# DotCrypt.net
KiCad netlist of a schematic drawn in EAGLE
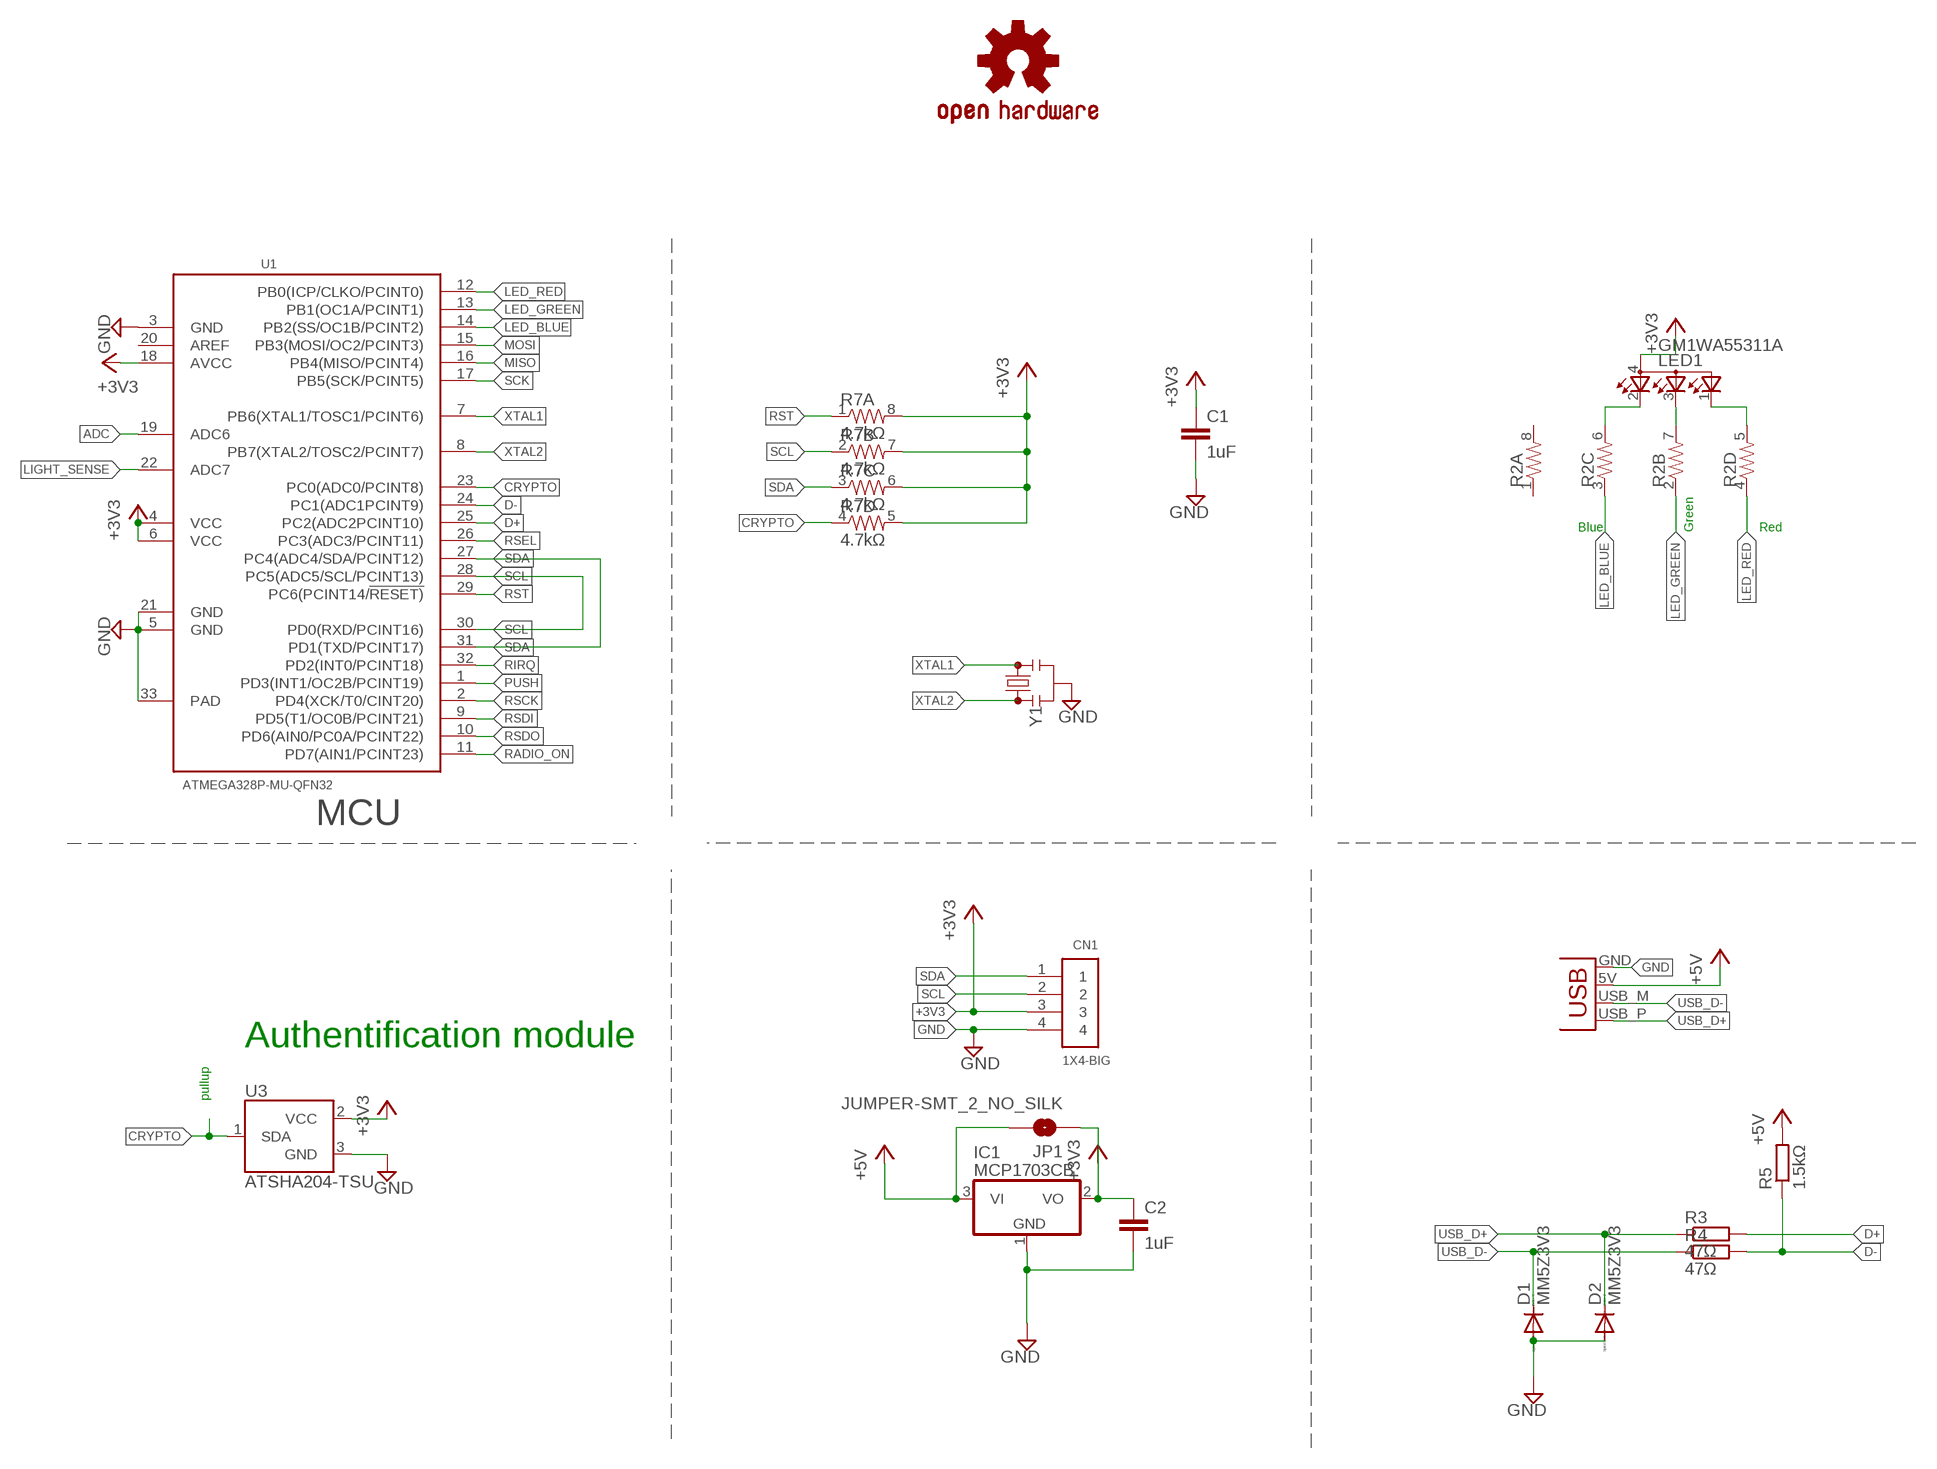
[diagram p0: schematic, sheet 1]

(export (version "E")
  (design (tool "Eeschema 10.0.6"))
  (components
    (comp (ref "C1")
      (value "1uF")
      (footprint "eagle-import:C0603")
      (libsource (lib "eagle-import") (part "C-EUC0603"))
    )
    (comp (ref "C2")
      (value "1uF")
      (footprint "eagle-import:C0603")
      (libsource (lib "eagle-import") (part "C-EUC0603"))
    )
    (comp (ref "CN1")
      (value "1X4-BIG")
      (footprint "eagle-import:1X04-BIG")
      (libsource (lib "eagle-import") (part "1X4-BIG"))
    )
    (comp (ref "D1")
      (value "MM5Z3V3")
      (footprint "eagle-import:SOD523")
      (libsource (lib "eagle-import") (part "DIODE-SOD523"))
    )
    (comp (ref "D2")
      (value "MM5Z3V3")
      (footprint "eagle-import:SOD523")
      (libsource (lib "eagle-import") (part "DIODE-SOD523"))
    )
    (comp (ref "IC1")
      (value "MCP1703CB")
      (footprint "eagle-import:SOT23")
      (libsource (lib "eagle-import") (part "MCP1703CB"))
    )
    (comp (ref "JP1")
      (value "JUMPER-SMT_2_NO_SILK")
      (footprint "eagle-import:SMT-JUMPER_2_NO_SILK")
      (libsource (lib "eagle-import") (part "JUMPER-SMT_2_NO_SILK"))
    )
    (comp (ref "JP3")
      (value "USBPCB")
      (footprint "eagle-import:USB-A-PCB")
      (libsource (lib "eagle-import") (part "USBPCB"))
    )
    (comp (ref "LED1")
      (value "GM1WA55311A")
      (footprint "eagle-import:GM1WA55311A")
      (libsource (lib "eagle-import") (part "GM1WA55311A"))
    )
    (comp (ref "LOGO1")
      (value "OSHW-LOGOS")
      (footprint "eagle-import:OSHW-LOGO-S")
      (libsource (lib "eagle-import") (part "OSHW-LOGOS"))
    )
    (comp (ref "R2")
      (value "RESISTOR-ARRAY0603-ARV")
      (footprint "eagle-import:0603-ARV")
      (libsource (lib "eagle-import") (part "RESISTOR-ARRAY0603-ARV"))
    )
    (comp (ref "R3")
      (value "47Ω")
      (footprint "eagle-import:R0603")
      (libsource (lib "eagle-import") (part "R-EU_R0603"))
    )
    (comp (ref "R4")
      (value "47Ω")
      (footprint "eagle-import:R0603")
      (libsource (lib "eagle-import") (part "R-EU_R0603"))
    )
    (comp (ref "R5")
      (value "1.5kΩ")
      (footprint "eagle-import:R0603")
      (libsource (lib "eagle-import") (part "R-EU_R0603"))
    )
    (comp (ref "R7")
      (value "4.7kΩ")
      (footprint "eagle-import:0603-ARV")
      (libsource (lib "eagle-import") (part "RESISTOR-ARRAY0603-ARV"))
    )
    (comp (ref "U1")
      (value "ATMEGA328P-MU-QFN32")
      (footprint "eagle-import:QFN32G-0.5-5X5MM")
      (fields (field (name "MPN") "ATMEGA328P-MU"))
      (libsource (lib "eagle-import") (part "MCU-ATMEGA328P-MU(QFN32)"))
    )
    (comp (ref "U3")
      (value "ATSHA204-TSU")
      (footprint "eagle-import:SOT23-3")
      (libsource (lib "eagle-import") (part "ATSHA204-TSU"))
    )
    (comp (ref "Y1")
      (value "RESONATORSMD-3.2X1.3")
      (footprint "eagle-import:RESONATOR-SMD-3.2X1.3")
      (libsource (lib "eagle-import") (part "RESONATORSMD-3.2X1.3"))
    )
  )
  (nets
    (net (code "1") (name "+3V3") (class "Default")
      (node (ref "C1") (pin "1") (pinfunction "1_1") (pintype "passive"))
      (node (ref "C2") (pin "1") (pinfunction "1_1") (pintype "passive"))
      (node (ref "CN1") (pin "3") (pinfunction "3_3") (pintype "bidirectional"))
      (node (ref "IC1") (pin "2") (pinfunction "VO_2") (pintype "passive"))
      (node (ref "JP1") (pin "1") (pinfunction "1_1") (pintype "passive"))
      (node (ref "LED1") (pin "4") (pinfunction "A_4") (pintype "passive"))
      (node (ref "R7") (pin "5") (pinfunction "2_5") (pintype "passive"))
      (node (ref "R7") (pin "6") (pinfunction "2_6") (pintype "passive"))
      (node (ref "R7") (pin "7") (pinfunction "2_7") (pintype "passive"))
      (node (ref "R7") (pin "8") (pinfunction "2_8") (pintype "passive"))
      (node (ref "U1") (pin "18") (pinfunction "AVCC_18") (pintype "bidirectional"))
      (node (ref "U1") (pin "4") (pinfunction "VCC_4") (pintype "bidirectional"))
      (node (ref "U1") (pin "6") (pinfunction "VCC_6") (pintype "bidirectional"))
      (node (ref "U3") (pin "2") (pinfunction "VCC_2") (pintype "bidirectional"))
    )
    (net (code "2") (name "+5V") (class "Default")
      (node (ref "IC1") (pin "3") (pinfunction "VI_3") (pintype "input"))
      (node (ref "JP1") (pin "2") (pinfunction "2_2") (pintype "passive"))
      (node (ref "JP3") (pin "5V") (pinfunction "VBUS_5V") (pintype "bidirectional"))
      (node (ref "R5") (pin "2") (pinfunction "2_2") (pintype "passive"))
    )
    (net (code "3") (name "ADC") (class "Default")
      (node (ref "U1") (pin "19") (pinfunction "ADC6_19") (pintype "bidirectional"))
    )
    (net (code "4") (name "CRYPTO") (class "Default")
      (node (ref "R7") (pin "4") (pinfunction "1_4") (pintype "passive"))
      (node (ref "U1") (pin "23") (pinfunction "PC0(ADC0/PCINT8)_23") (pintype "bidirectional"))
      (node (ref "U3") (pin "1") (pinfunction "SDA_1") (pintype "bidirectional"))
    )
    (net (code "5") (name "D+") (class "Default")
      (node (ref "R3") (pin "2") (pinfunction "2_2") (pintype "passive"))
      (node (ref "U1") (pin "25") (pinfunction "PC2(ADC2PCINT10)_25") (pintype "bidirectional"))
    )
    (net (code "6") (name "D-") (class "Default")
      (node (ref "R4") (pin "2") (pinfunction "2_2") (pintype "passive"))
      (node (ref "R5") (pin "1") (pinfunction "1_1") (pintype "passive"))
      (node (ref "U1") (pin "24") (pinfunction "PC1(ADC1PCINT9)_24") (pintype "bidirectional"))
    )
    (net (code "7") (name "GND") (class "Default")
      (node (ref "C1") (pin "2") (pinfunction "2_2") (pintype "passive"))
      (node (ref "C2") (pin "2") (pinfunction "2_2") (pintype "passive"))
      (node (ref "CN1") (pin "4") (pinfunction "4_4") (pintype "bidirectional"))
      (node (ref "D1") (pin "A") (pinfunction "A_A") (pintype "passive"))
      (node (ref "D2") (pin "A") (pinfunction "A_A") (pintype "passive"))
      (node (ref "IC1") (pin "1") (pinfunction "GND_1") (pintype "passive"))
      (node (ref "JP3") (pin "GND") (pinfunction "GND_GND") (pintype "bidirectional"))
      (node (ref "U1") (pin "21") (pinfunction "GND_21") (pintype "bidirectional"))
      (node (ref "U1") (pin "3") (pinfunction "GND_3") (pintype "bidirectional"))
      (node (ref "U1") (pin "33") (pinfunction "PAD_33") (pintype "bidirectional"))
      (node (ref "U1") (pin "5") (pinfunction "GND_5") (pintype "bidirectional"))
      (node (ref "U3") (pin "3") (pinfunction "GND_3") (pintype "bidirectional"))
      (node (ref "Y1") (pin "2") (pinfunction "2_2") (pintype "passive"))
    )
    (net (code "8") (name "LED_BLUE") (class "Default")
      (node (ref "R2") (pin "3") (pinfunction "1_3") (pintype "passive"))
      (node (ref "U1") (pin "14") (pinfunction "PB2(SS/OC1B/PCINT2)_14") (pintype "bidirectional"))
    )
    (net (code "9") (name "LED_GREEN") (class "Default")
      (node (ref "R2") (pin "2") (pinfunction "1_2") (pintype "passive"))
      (node (ref "U1") (pin "13") (pinfunction "PB1(OC1A/PCINT1)_13") (pintype "bidirectional"))
    )
    (net (code "10") (name "LED_RED") (class "Default")
      (node (ref "R2") (pin "4") (pinfunction "1_4") (pintype "passive"))
      (node (ref "U1") (pin "12") (pinfunction "PB0(ICP/CLKO/PCINT0)_12") (pintype "bidirectional"))
    )
    (net (code "11") (name "LIGHT_SENSE") (class "Default")
      (node (ref "U1") (pin "22") (pinfunction "ADC7_22") (pintype "bidirectional"))
    )
    (net (code "12") (name "MISO") (class "Default")
      (node (ref "U1") (pin "16") (pinfunction "PB4(MISO/PCINT4)_16") (pintype "bidirectional"))
    )
    (net (code "13") (name "MOSI") (class "Default")
      (node (ref "U1") (pin "15") (pinfunction "PB3(MOSI/OC2/PCINT3)_15") (pintype "bidirectional"))
    )
    (net (code "14") (name "Net-(LED1-CBLUE)") (class "Default")
      (node (ref "LED1") (pin "3") (pinfunction "CBLUE_3") (pintype "passive"))
      (node (ref "R2") (pin "7") (pinfunction "2_7") (pintype "passive"))
    )
    (net (code "15") (name "Net-(LED1-CGREEN)") (class "Default")
      (node (ref "LED1") (pin "1") (pinfunction "CGREEN_1") (pintype "passive"))
      (node (ref "R2") (pin "5") (pinfunction "2_5") (pintype "passive"))
    )
    (net (code "16") (name "Net-(LED1-CRED)") (class "Default")
      (node (ref "LED1") (pin "2") (pinfunction "CRED_2") (pintype "passive"))
      (node (ref "R2") (pin "6") (pinfunction "2_6") (pintype "passive"))
    )
    (net (code "17") (name "PUSH") (class "Default")
      (node (ref "U1") (pin "1") (pinfunction "PD3(INT1/OC2B/PCINT19)_1") (pintype "bidirectional"))
    )
    (net (code "18") (name "RADIO_ON") (class "Default")
      (node (ref "U1") (pin "11") (pinfunction "PD7(AIN1/PCINT23)_11") (pintype "bidirectional"))
    )
    (net (code "19") (name "RIRQ") (class "Default")
      (node (ref "U1") (pin "32") (pinfunction "PD2(INT0/PCINT18)_32") (pintype "bidirectional"))
    )
    (net (code "20") (name "RSCK") (class "Default")
      (node (ref "U1") (pin "2") (pinfunction "PD4(XCK/T0/CINT20)_2") (pintype "bidirectional"))
    )
    (net (code "21") (name "RSDI") (class "Default")
      (node (ref "U1") (pin "9") (pinfunction "PD5(T1/OC0B/PCINT21)_9") (pintype "bidirectional"))
    )
    (net (code "22") (name "RSDO") (class "Default")
      (node (ref "U1") (pin "10") (pinfunction "PD6(AIN0/PC0A/PCINT22)_10") (pintype "bidirectional"))
    )
    (net (code "23") (name "RSEL") (class "Default")
      (node (ref "U1") (pin "26") (pinfunction "PC3(ADC3/PCINT11)_26") (pintype "bidirectional"))
    )
    (net (code "24") (name "RST") (class "Default")
      (node (ref "R7") (pin "1") (pinfunction "1_1") (pintype "passive"))
      (node (ref "U1") (pin "29") (pinfunction "PC6(PCINT14/~{RESET})_29") (pintype "bidirectional"))
    )
    (net (code "25") (name "SCK") (class "Default")
      (node (ref "U1") (pin "17") (pinfunction "PB5(SCK/PCINT5)_17") (pintype "bidirectional"))
    )
    (net (code "26") (name "SCL") (class "Default")
      (node (ref "CN1") (pin "2") (pinfunction "2_2") (pintype "bidirectional"))
      (node (ref "R7") (pin "2") (pinfunction "1_2") (pintype "passive"))
      (node (ref "U1") (pin "28") (pinfunction "PC5(ADC5/SCL/PCINT13)_28") (pintype "bidirectional"))
      (node (ref "U1") (pin "30") (pinfunction "PD0(RXD/PCINT16)_30") (pintype "bidirectional"))
    )
    (net (code "27") (name "SDA") (class "Default")
      (node (ref "CN1") (pin "1") (pinfunction "1_1") (pintype "bidirectional"))
      (node (ref "R7") (pin "3") (pinfunction "1_3") (pintype "passive"))
      (node (ref "U1") (pin "27") (pinfunction "PC4(ADC4/SDA/PCINT12)_27") (pintype "bidirectional"))
      (node (ref "U1") (pin "31") (pinfunction "PD1(TXD/PCINT17)_31") (pintype "bidirectional"))
    )
    (net (code "28") (name "USB_D+") (class "Default")
      (node (ref "D2") (pin "C") (pinfunction "C_C") (pintype "passive"))
      (node (ref "JP3") (pin "USB_P") (pinfunction "D+_USB_P") (pintype "bidirectional"))
      (node (ref "R3") (pin "1") (pinfunction "1_1") (pintype "passive"))
    )
    (net (code "29") (name "USB_D-") (class "Default")
      (node (ref "D1") (pin "C") (pinfunction "C_C") (pintype "passive"))
      (node (ref "JP3") (pin "USB_M") (pinfunction "D-_USB_M") (pintype "bidirectional"))
      (node (ref "R4") (pin "1") (pinfunction "1_1") (pintype "passive"))
    )
    (net (code "30") (name "XTAL1") (class "Default")
      (node (ref "U1") (pin "7") (pinfunction "PB6(XTAL1/TOSC1/PCINT6)_7") (pintype "bidirectional"))
      (node (ref "Y1") (pin "3") (pinfunction "3_3") (pintype "passive"))
    )
    (net (code "31") (name "XTAL2") (class "Default")
      (node (ref "U1") (pin "8") (pinfunction "PB7(XTAL2/TOSC2/PCINT7)_8") (pintype "bidirectional"))
      (node (ref "Y1") (pin "1") (pinfunction "1_1") (pintype "passive"))
    )
    (net (code "32") (name "unconnected-(R2-Pad1)") (class "Default")
      (node (ref "R2") (pin "1") (pinfunction "1_1") (pintype "passive"))
    )
    (net (code "33") (name "unconnected-(R2A-2-Pad8)") (class "Default")
      (node (ref "R2") (pin "8") (pinfunction "2_8") (pintype "passive"))
    )
    (net (code "34") (name "unconnected-(U1-AREF-Pad20)") (class "Default")
      (node (ref "U1") (pin "20") (pinfunction "AREF_20") (pintype "bidirectional"))
    )
  )
)
